# jelly_encoder_Board.net
KiCad netlist of a schematic drawn in EAGLE
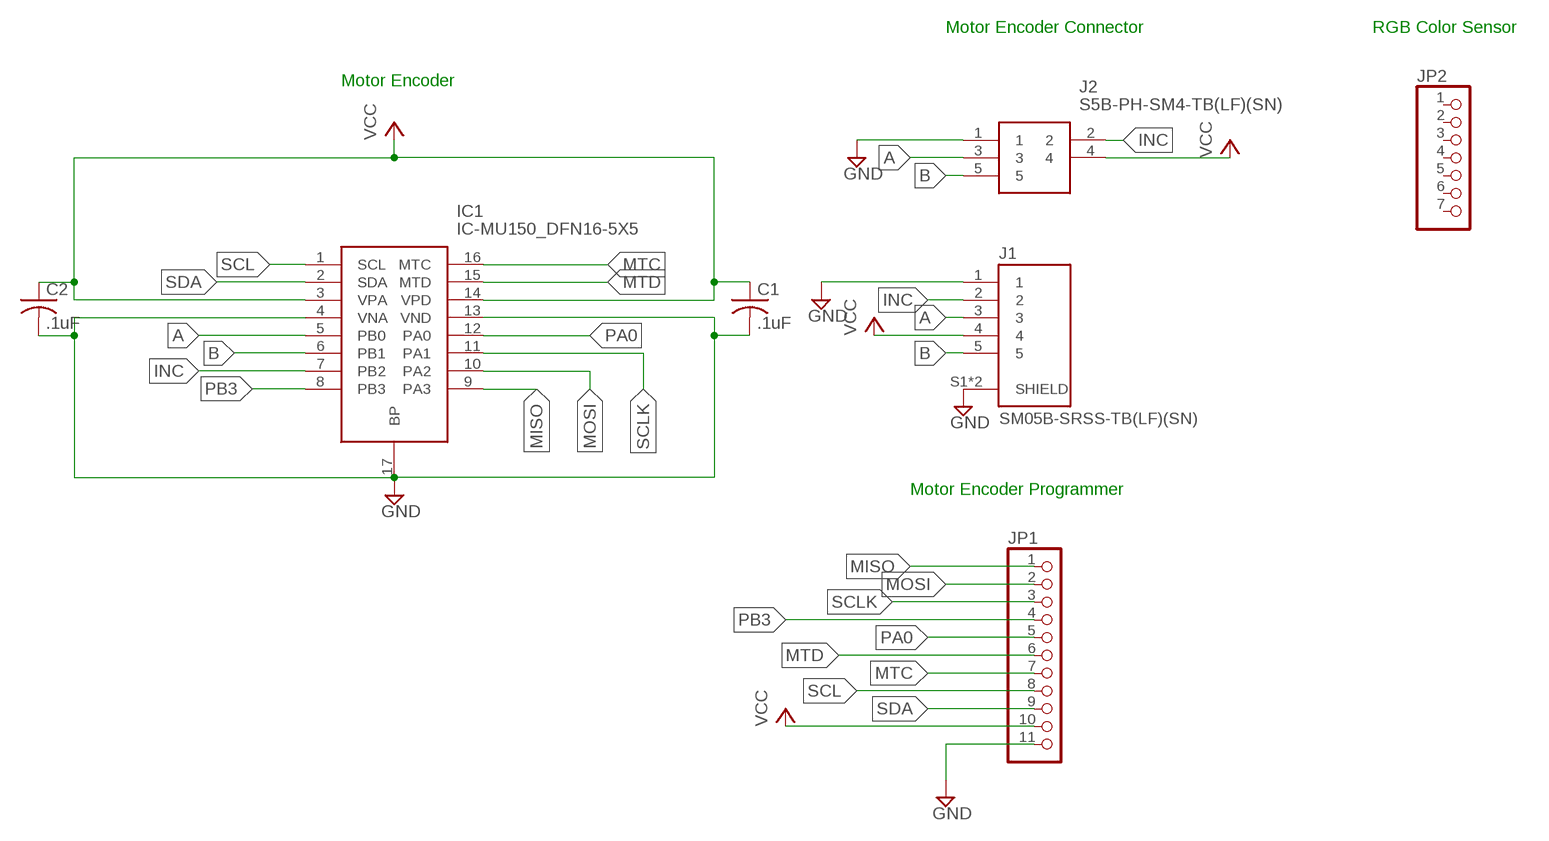
[diagram p0: schematic, sheet 1]

(export (version "E")
  (design (tool "Eeschema 10.0.6"))
  (components
    (comp (ref "C1")
      (value ".1uF")
      (footprint "eagle-import:C0603")
      (libsource (lib "eagle-import") (part "C-USC0603"))
    )
    (comp (ref "C2")
      (value ".1uF")
      (footprint "eagle-import:C0603")
      (libsource (lib "eagle-import") (part "C-USC0603"))
    )
    (comp (ref "IC1")
      (value "IC-MU150_DFN16-5X5")
      (footprint "eagle-import:SON50P500X500X100-17N")
      (fields (field (name "MANUFACTURER_PART_NUMBER") "IC-MU150 DFN16-5X5"))
      (libsource (lib "eagle-import") (part "IC-MU150_DFN16-5X5"))
    )
    (comp (ref "J1")
      (value "SM05B-SRSS-TB(LF)(SN)")
      (footprint "eagle-import:JST_SM05B-SRSS-TB(LF)(SN)")
      (fields (field (name "MF") "JST Sales") (field (name "MP") "SM05B-SRSS-TB_LF__SN_"))
      (libsource (lib "eagle-import") (part "SM05B-SRSS-TB(LF)(SN)"))
    )
    (comp (ref "J2")
      (value "S5B-PH-SM4-TB(LF)(SN)")
      (footprint "eagle-import:S5B-PH-SM4-TB_1")
      (libsource (lib "eagle-import") (part "S5B-PH-SM4-TB(LF)(SN)"))
    )
    (comp (ref "JP1")
      (value "PINHD-1X11/90")
      (footprint "eagle-import:1X11_90")
      (libsource (lib "eagle-import") (part "PINHD-1X11/90"))
    )
    (comp (ref "JP2")
      (value "PINHD-1X7/90")
      (footprint "eagle-import:1X07_90")
      (libsource (lib "eagle-import") (part "PINHD-1X7/90"))
    )
  )
  (nets
    (net (code "1") (name "A") (class "Default")
      (node (ref "IC1") (pin "5") (pinfunction "PB0_5") (pintype "bidirectional"))
      (node (ref "J1") (pin "3") (pinfunction "3_3") (pintype "passive"))
      (node (ref "J2") (pin "3") (pinfunction "3_3") (pintype "bidirectional"))
    )
    (net (code "2") (name "B") (class "Default")
      (node (ref "IC1") (pin "6") (pinfunction "PB1_6") (pintype "bidirectional"))
      (node (ref "J1") (pin "5") (pinfunction "5_5") (pintype "passive"))
      (node (ref "J2") (pin "5") (pinfunction "5_5") (pintype "bidirectional"))
    )
    (net (code "3") (name "GND") (class "Default")
      (node (ref "C1") (pin "2") (pinfunction "2_2") (pintype "passive"))
      (node (ref "C2") (pin "2") (pinfunction "2_2") (pintype "passive"))
      (node (ref "IC1") (pin "13") (pinfunction "VND_13") (pintype "bidirectional"))
      (node (ref "IC1") (pin "17") (pinfunction "BP_17") (pintype "bidirectional"))
      (node (ref "IC1") (pin "4") (pinfunction "VNA_4") (pintype "bidirectional"))
      (node (ref "J1") (pin "1") (pinfunction "1_1") (pintype "passive"))
      (node (ref "J1") (pin "S1") (pinfunction "SHIELD_S1") (pintype "passive"))
      (node (ref "J1") (pin "S2") (pinfunction "SHIELD_S2") (pintype "passive"))
      (node (ref "J2") (pin "1") (pinfunction "1_1") (pintype "bidirectional"))
      (node (ref "JP1") (pin "11") (pinfunction "11_11") (pintype "passive"))
    )
    (net (code "4") (name "INC") (class "Default")
      (node (ref "IC1") (pin "7") (pinfunction "PB2_7") (pintype "bidirectional"))
      (node (ref "J1") (pin "2") (pinfunction "2_2") (pintype "passive"))
      (node (ref "J2") (pin "2") (pinfunction "2_2") (pintype "bidirectional"))
    )
    (net (code "5") (name "MISO") (class "Default")
      (node (ref "IC1") (pin "9") (pinfunction "PA3_9") (pintype "bidirectional"))
      (node (ref "JP1") (pin "1") (pinfunction "1_1") (pintype "passive"))
    )
    (net (code "6") (name "MOSI") (class "Default")
      (node (ref "IC1") (pin "10") (pinfunction "PA2_10") (pintype "bidirectional"))
      (node (ref "JP1") (pin "2") (pinfunction "2_2") (pintype "passive"))
    )
    (net (code "7") (name "MTC") (class "Default")
      (node (ref "IC1") (pin "16") (pinfunction "MTC_16") (pintype "bidirectional"))
      (node (ref "JP1") (pin "7") (pinfunction "7_7") (pintype "passive"))
    )
    (net (code "8") (name "MTD") (class "Default")
      (node (ref "IC1") (pin "15") (pinfunction "MTD_15") (pintype "bidirectional"))
      (node (ref "JP1") (pin "6") (pinfunction "6_6") (pintype "passive"))
    )
    (net (code "9") (name "PA0") (class "Default")
      (node (ref "IC1") (pin "12") (pinfunction "PA0_12") (pintype "bidirectional"))
      (node (ref "JP1") (pin "5") (pinfunction "5_5") (pintype "passive"))
    )
    (net (code "10") (name "PB3") (class "Default")
      (node (ref "IC1") (pin "8") (pinfunction "PB3_8") (pintype "bidirectional"))
      (node (ref "JP1") (pin "4") (pinfunction "4_4") (pintype "passive"))
    )
    (net (code "11") (name "SCL") (class "Default")
      (node (ref "IC1") (pin "1") (pinfunction "SCL_1") (pintype "bidirectional"))
      (node (ref "JP1") (pin "8") (pinfunction "8_8") (pintype "passive"))
    )
    (net (code "12") (name "SCLK") (class "Default")
      (node (ref "IC1") (pin "11") (pinfunction "PA1_11") (pintype "bidirectional"))
      (node (ref "JP1") (pin "3") (pinfunction "3_3") (pintype "passive"))
    )
    (net (code "13") (name "SDA") (class "Default")
      (node (ref "IC1") (pin "2") (pinfunction "SDA_2") (pintype "bidirectional"))
      (node (ref "JP1") (pin "9") (pinfunction "9_9") (pintype "passive"))
    )
    (net (code "14") (name "VCC") (class "Default")
      (node (ref "C1") (pin "1") (pinfunction "1_1") (pintype "passive"))
      (node (ref "C2") (pin "1") (pinfunction "1_1") (pintype "passive"))
      (node (ref "IC1") (pin "14") (pinfunction "VPD_14") (pintype "bidirectional"))
      (node (ref "IC1") (pin "3") (pinfunction "VPA_3") (pintype "bidirectional"))
      (node (ref "J1") (pin "4") (pinfunction "4_4") (pintype "passive"))
      (node (ref "J2") (pin "4") (pinfunction "4_4") (pintype "bidirectional"))
      (node (ref "JP1") (pin "10") (pinfunction "10_10") (pintype "passive"))
    )
    (net (code "15") (name "unconnected-(JP2-Pad1)") (class "Default")
      (node (ref "JP2") (pin "1") (pinfunction "1_1") (pintype "passive"))
    )
    (net (code "16") (name "unconnected-(JP2-Pad2)") (class "Default")
      (node (ref "JP2") (pin "2") (pinfunction "2_2") (pintype "passive"))
    )
    (net (code "17") (name "unconnected-(JP2-Pad3)") (class "Default")
      (node (ref "JP2") (pin "3") (pinfunction "3_3") (pintype "passive"))
    )
    (net (code "18") (name "unconnected-(JP2-Pad4)") (class "Default")
      (node (ref "JP2") (pin "4") (pinfunction "4_4") (pintype "passive"))
    )
    (net (code "19") (name "unconnected-(JP2-Pad5)") (class "Default")
      (node (ref "JP2") (pin "5") (pinfunction "5_5") (pintype "passive"))
    )
    (net (code "20") (name "unconnected-(JP2-Pad6)") (class "Default")
      (node (ref "JP2") (pin "6") (pinfunction "6_6") (pintype "passive"))
    )
    (net (code "21") (name "unconnected-(JP2-Pad7)") (class "Default")
      (node (ref "JP2") (pin "7") (pinfunction "7_7") (pintype "passive"))
    )
  )
)
